# DazzeLiteSch.net
KiCad netlist of a schematic drawn in EAGLE
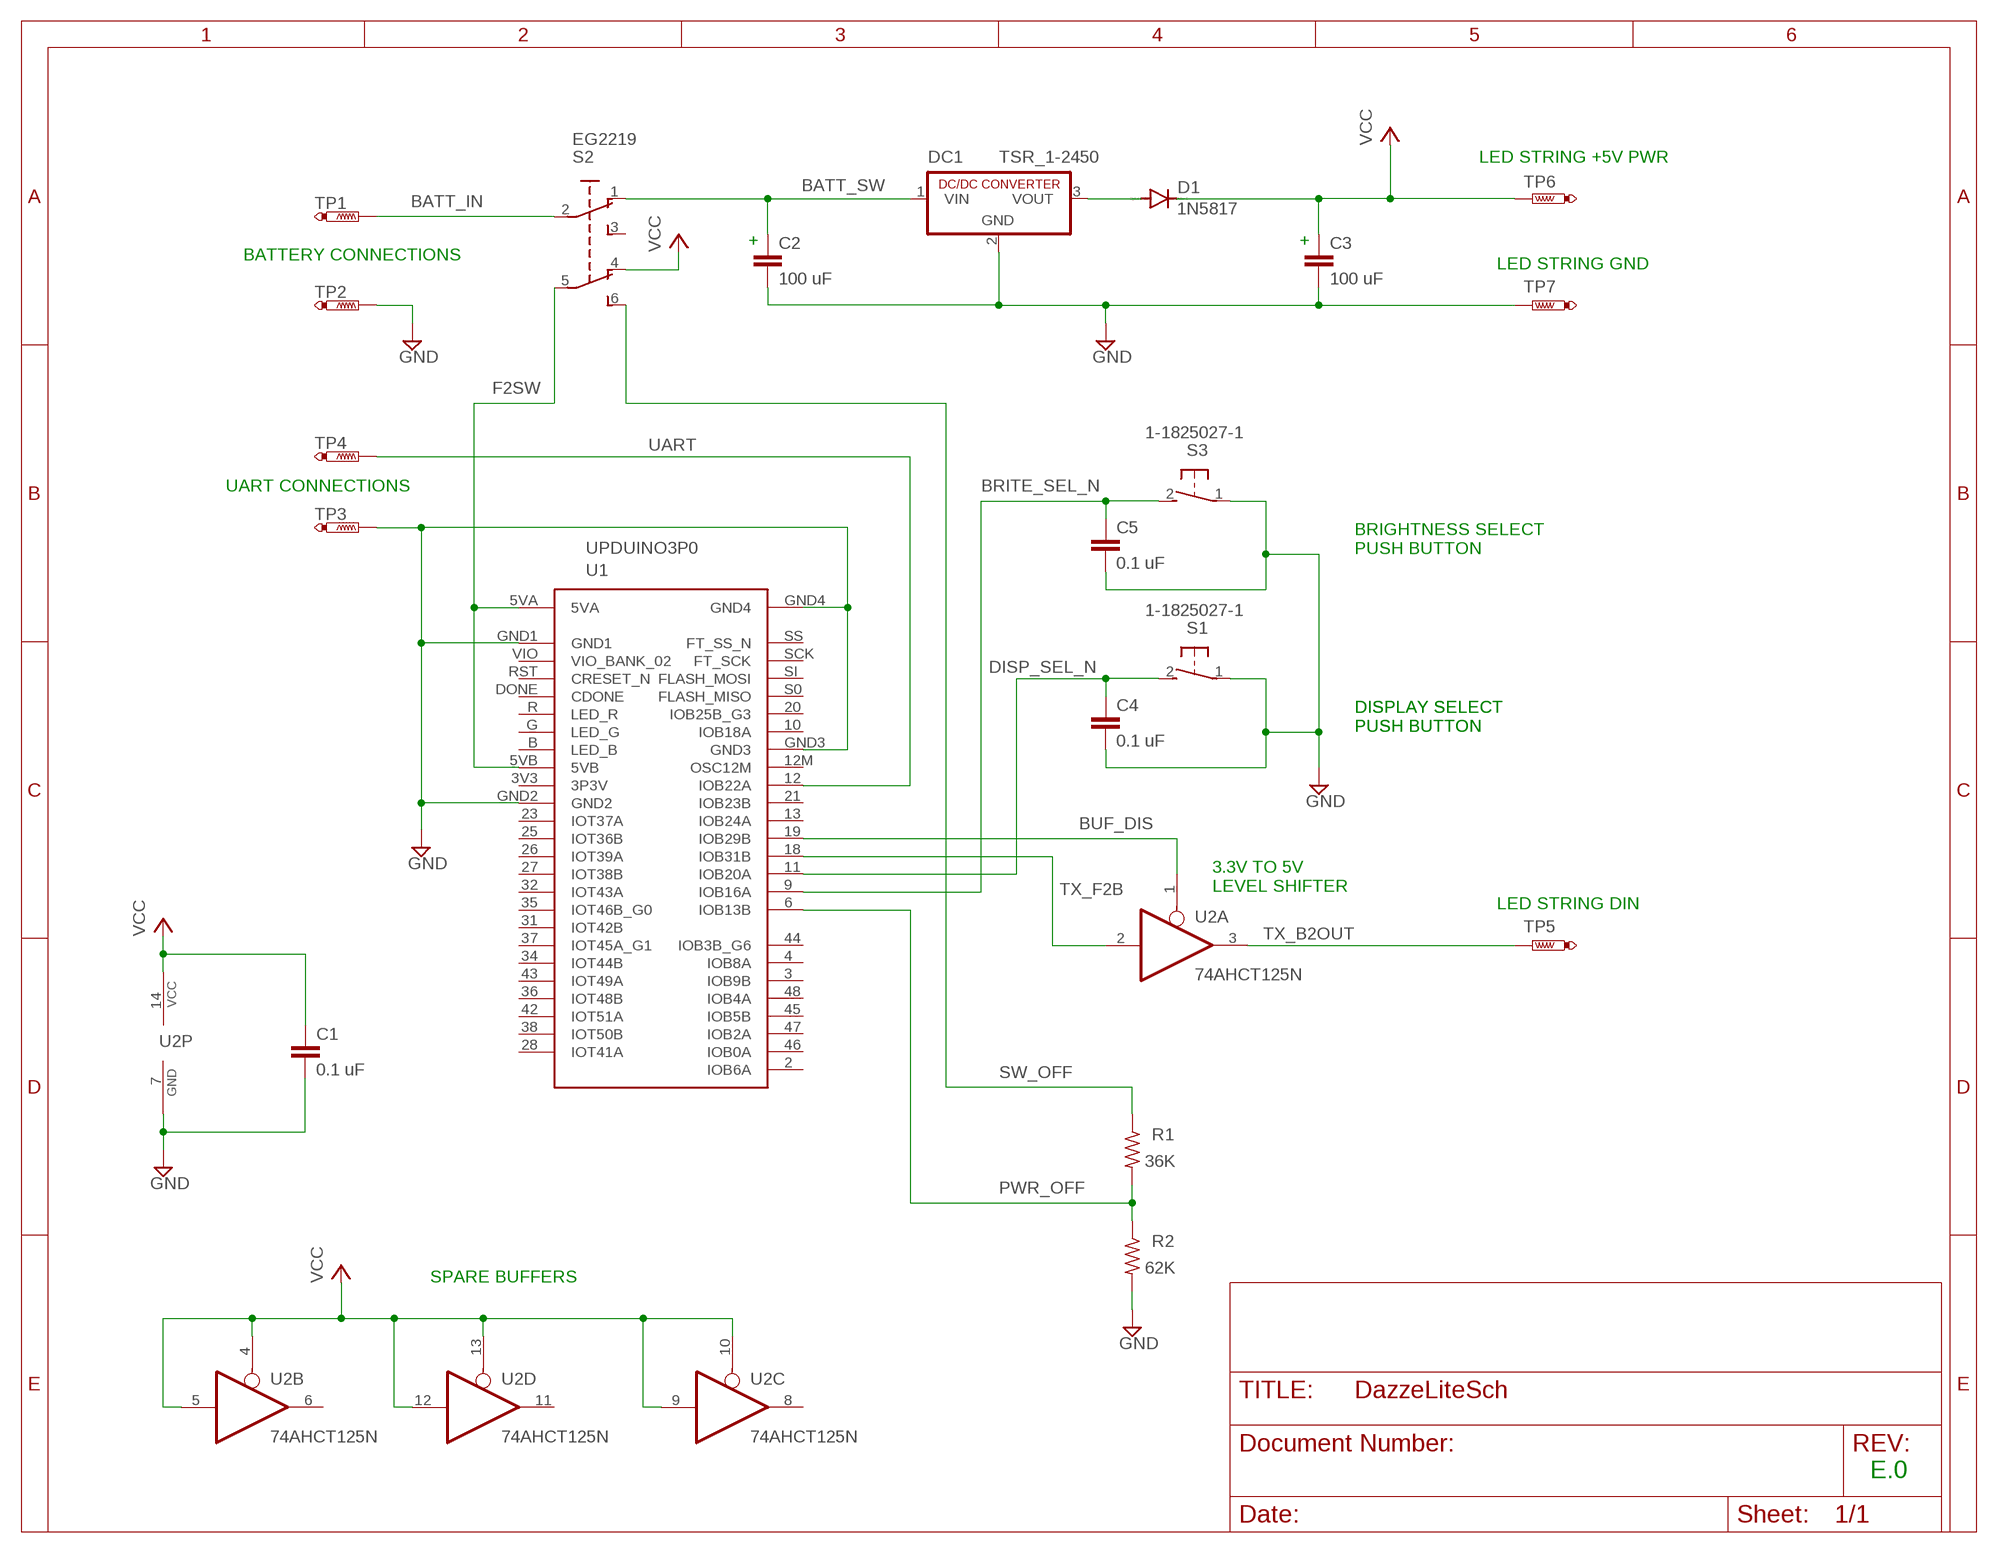
[diagram p0: schematic, sheet 1]

(export (version "E")
  (design (tool "Eeschema 10.0.6"))
  (components
    (comp (ref "C1")
      (value "0.1 uF")
      (footprint "eagle-import:C2.5-3")
      (libsource (lib "eagle-import") (part "C2,5-3"))
    )
    (comp (ref "C2")
      (value "100 uF")
      (footprint "eagle-import:C2.5-6")
      (libsource (lib "eagle-import") (part "C2.5/6"))
    )
    (comp (ref "C3")
      (value "100 uF")
      (footprint "eagle-import:C2.5-6")
      (libsource (lib "eagle-import") (part "C2.5/6"))
    )
    (comp (ref "C4")
      (value "0.1 uF")
      (footprint "eagle-import:C2.5-3")
      (libsource (lib "eagle-import") (part "C2,5-3"))
    )
    (comp (ref "C5")
      (value "0.1 uF")
      (footprint "eagle-import:C2.5-3")
      (libsource (lib "eagle-import") (part "C2,5-3"))
    )
    (comp (ref "D1")
      (value "1N5817")
      (footprint "eagle-import:DO41-10")
      (libsource (lib "eagle-import") (part "DIODE-DO41-10"))
    )
    (comp (ref "DC1")
      (value "TSR_1-2450")
      (footprint "eagle-import:SIP3")
      (libsource (lib "eagle-import") (part "TSR_1-2450"))
    )
    (comp (ref "R1")
      (value "36K")
      (footprint "eagle-import:0204_7")
      (libsource (lib "eagle-import") (part "R-US_0204/7"))
    )
    (comp (ref "R2")
      (value "62K")
      (footprint "eagle-import:0204_7")
      (libsource (lib "eagle-import") (part "R-US_0204/7"))
    )
    (comp (ref "S1")
      (value "1-1825027-1")
      (footprint "eagle-import:B3F-31XX")
      (libsource (lib "eagle-import") (part "1-1825027-1"))
    )
    (comp (ref "S2")
      (value "EG2219")
      (footprint "eagle-import:DPDT157")
      (libsource (lib "eagle-import") (part "EG2219"))
    )
    (comp (ref "S3")
      (value "1-1825027-1")
      (footprint "eagle-import:B3F-31XX")
      (libsource (lib "eagle-import") (part "1-1825027-1"))
    )
    (comp (ref "TP1")
      (value "PTR1PAD1-13")
      (footprint "eagle-import:P1-13")
      (libsource (lib "eagle-import") (part "PTR1PAD1-13"))
    )
    (comp (ref "TP2")
      (value "PTR1PAD1-13")
      (footprint "eagle-import:P1-13")
      (libsource (lib "eagle-import") (part "PTR1PAD1-13"))
    )
    (comp (ref "TP3")
      (value "PTR1PAD1-13")
      (footprint "eagle-import:P1-13")
      (libsource (lib "eagle-import") (part "PTR1PAD1-13"))
    )
    (comp (ref "TP4")
      (value "PTR1PAD1-13")
      (footprint "eagle-import:P1-13")
      (libsource (lib "eagle-import") (part "PTR1PAD1-13"))
    )
    (comp (ref "TP5")
      (value "PTR1PAD1-13")
      (footprint "eagle-import:P1-13")
      (libsource (lib "eagle-import") (part "PTR1PAD1-13"))
    )
    (comp (ref "TP6")
      (value "PTR1PAD1-13")
      (footprint "eagle-import:P1-13")
      (libsource (lib "eagle-import") (part "PTR1PAD1-13"))
    )
    (comp (ref "TP7")
      (value "PTR1PAD1-13")
      (footprint "eagle-import:P1-13")
      (libsource (lib "eagle-import") (part "PTR1PAD1-13"))
    )
    (comp (ref "U1")
      (value "UPDUINO3P0")
      (footprint "eagle-import:UPDUINO3P0")
      (libsource (lib "eagle-import") (part "UPDUINO3P0"))
    )
    (comp (ref "U2")
      (value "74AHCT125N")
      (footprint "eagle-import:DIL14")
      (libsource (lib "eagle-import") (part "74125NAHCT"))
    )
  )
  (nets
    (net (code "1") (name "/BATT_IN") (class "Default")
      (node (ref "S2") (pin "2") (pinfunction "P_2") (pintype "passive"))
      (node (ref "TP1") (pin "TP") (pinfunction "TP_TP") (pintype "input"))
    )
    (net (code "2") (name "/BATT_SW") (class "Default")
      (node (ref "C2") (pin "1") (pinfunction "1_1") (pintype "passive"))
      (node (ref "DC1") (pin "1") (pinfunction "VIN_1") (pintype "passive"))
      (node (ref "S2") (pin "1") (pinfunction "O_1") (pintype "passive"))
    )
    (net (code "3") (name "/BRITE_SEL_N") (class "Default")
      (node (ref "C5") (pin "1") (pinfunction "1_1") (pintype "passive"))
      (node (ref "S3") (pin "2") (pinfunction "S_2") (pintype "passive"))
      (node (ref "U1") (pin "9") (pinfunction "IOB16A_9") (pintype "bidirectional"))
    )
    (net (code "4") (name "/BUF_DIS") (class "Default")
      (node (ref "U1") (pin "19") (pinfunction "IOB29B_19") (pintype "bidirectional"))
      (node (ref "U2") (pin "1") (pinfunction "OE_1") (pintype "input"))
    )
    (net (code "5") (name "/DISP_SEL_N") (class "Default")
      (node (ref "C4") (pin "1") (pinfunction "1_1") (pintype "passive"))
      (node (ref "S1") (pin "2") (pinfunction "S_2") (pintype "passive"))
      (node (ref "U1") (pin "11") (pinfunction "IOB20A_11") (pintype "bidirectional"))
    )
    (net (code "6") (name "/F2SW") (class "Default")
      (node (ref "S2") (pin "5") (pinfunction "P1_5") (pintype "passive"))
      (node (ref "U1") (pin "5VA") (pinfunction "5VA_5VA") (pintype "power_in"))
      (node (ref "U1") (pin "5VB") (pinfunction "5VB_5VB") (pintype "power_in"))
    )
    (net (code "7") (name "/PWR_OFF") (class "Default")
      (node (ref "R1") (pin "2") (pinfunction "2_2") (pintype "passive"))
      (node (ref "R2") (pin "1") (pinfunction "1_1") (pintype "passive"))
      (node (ref "U1") (pin "6") (pinfunction "IOB13B_6") (pintype "bidirectional"))
    )
    (net (code "8") (name "/SW_OFF") (class "Default")
      (node (ref "R1") (pin "1") (pinfunction "1_1") (pintype "passive"))
      (node (ref "S2") (pin "6") (pinfunction "S1_6") (pintype "passive"))
    )
    (net (code "9") (name "/TX_B2OUT") (class "Default")
      (node (ref "TP5") (pin "TP") (pinfunction "TP_TP") (pintype "input"))
      (node (ref "U2") (pin "3") (pinfunction "O_3") (pintype "tri_state"))
    )
    (net (code "10") (name "/TX_F2B") (class "Default")
      (node (ref "U1") (pin "18") (pinfunction "IOB31B_18") (pintype "bidirectional"))
      (node (ref "U2") (pin "2") (pinfunction "I_2") (pintype "input"))
    )
    (net (code "11") (name "/UART") (class "Default")
      (node (ref "TP4") (pin "TP") (pinfunction "TP_TP") (pintype "input"))
      (node (ref "U1") (pin "12") (pinfunction "IOB22A_12") (pintype "bidirectional"))
    )
    (net (code "12") (name "GND") (class "Default")
      (node (ref "C1") (pin "2") (pinfunction "2_2") (pintype "passive"))
      (node (ref "C2") (pin "2") (pinfunction "2_2") (pintype "passive"))
      (node (ref "C3") (pin "2") (pinfunction "2_2") (pintype "passive"))
      (node (ref "C4") (pin "2") (pinfunction "2_2") (pintype "passive"))
      (node (ref "C5") (pin "2") (pinfunction "2_2") (pintype "passive"))
      (node (ref "DC1") (pin "2") (pinfunction "GND_2") (pintype "passive"))
      (node (ref "R2") (pin "2") (pinfunction "2_2") (pintype "passive"))
      (node (ref "S1") (pin "1") (pinfunction "P_1") (pintype "passive"))
      (node (ref "S3") (pin "1") (pinfunction "P_1") (pintype "passive"))
      (node (ref "TP2") (pin "TP") (pinfunction "TP_TP") (pintype "input"))
      (node (ref "TP3") (pin "TP") (pinfunction "TP_TP") (pintype "input"))
      (node (ref "TP7") (pin "TP") (pinfunction "TP_TP") (pintype "input"))
      (node (ref "U1") (pin "GND1") (pinfunction "GND1_GND1") (pintype "power_in"))
      (node (ref "U1") (pin "GND2") (pinfunction "GND2_GND2") (pintype "power_in"))
      (node (ref "U1") (pin "GND3") (pinfunction "GND3_GND3") (pintype "power_in"))
      (node (ref "U1") (pin "GND4") (pinfunction "GND4_GND4") (pintype "power_in"))
      (node (ref "U2") (pin "7") (pinfunction "GND_7") (pintype "power_in"))
    )
    (net (code "13") (name "Net-(DC1-VOUT)") (class "Default")
      (node (ref "D1") (pin "A") (pinfunction "A_A") (pintype "passive"))
      (node (ref "DC1") (pin "3") (pinfunction "VOUT_3") (pintype "passive"))
    )
    (net (code "14") (name "VCC") (class "Default")
      (node (ref "C1") (pin "1") (pinfunction "1_1") (pintype "passive"))
      (node (ref "C3") (pin "1") (pinfunction "1_1") (pintype "passive"))
      (node (ref "D1") (pin "C") (pinfunction "C_C") (pintype "passive"))
      (node (ref "S2") (pin "4") (pinfunction "O1_4") (pintype "passive"))
      (node (ref "TP6") (pin "TP") (pinfunction "TP_TP") (pintype "input"))
      (node (ref "U2") (pin "10") (pinfunction "OE_10") (pintype "input"))
      (node (ref "U2") (pin "12") (pinfunction "I_12") (pintype "input"))
      (node (ref "U2") (pin "13") (pinfunction "OE_13") (pintype "input"))
      (node (ref "U2") (pin "14") (pinfunction "VCC_14") (pintype "power_in"))
      (node (ref "U2") (pin "4") (pinfunction "OE_4") (pintype "input"))
      (node (ref "U2") (pin "5") (pinfunction "I_5") (pintype "input"))
      (node (ref "U2") (pin "9") (pinfunction "I_9") (pintype "input"))
    )
    (net (code "15") (name "unconnected-(S2-S-Pad3)") (class "Default")
      (node (ref "S2") (pin "3") (pinfunction "S_3") (pintype "passive"))
    )
    (net (code "16") (name "unconnected-(U1-3P3V-Pad3V3)") (class "Default")
      (node (ref "U1") (pin "3V3") (pinfunction "3P3V_3V3") (pintype "passive"))
    )
    (net (code "17") (name "unconnected-(U1-CDONE-PadDONE)") (class "Default")
      (node (ref "U1") (pin "DONE") (pinfunction "CDONE_DONE") (pintype "bidirectional"))
    )
    (net (code "18") (name "unconnected-(U1-CRESET_N-PadRST)") (class "Default")
      (node (ref "U1") (pin "RST") (pinfunction "CRESET_N_RST") (pintype "bidirectional"))
    )
    (net (code "19") (name "unconnected-(U1-FLASH_MISO-PadS0)") (class "Default")
      (node (ref "U1") (pin "S0") (pinfunction "FLASH_MISO_S0") (pintype "bidirectional"))
    )
    (net (code "20") (name "unconnected-(U1-FLASH_MOSI-PadSI)") (class "Default")
      (node (ref "U1") (pin "SI") (pinfunction "FLASH_MOSI_SI") (pintype "bidirectional"))
    )
    (net (code "21") (name "unconnected-(U1-FT_SCK-PadSCK)") (class "Default")
      (node (ref "U1") (pin "SCK") (pinfunction "FT_SCK_SCK") (pintype "bidirectional"))
    )
    (net (code "22") (name "unconnected-(U1-FT_SS_N-PadSS)") (class "Default")
      (node (ref "U1") (pin "SS") (pinfunction "FT_SS_N_SS") (pintype "bidirectional"))
    )
    (net (code "23") (name "unconnected-(U1-IOB0A-Pad46)") (class "Default")
      (node (ref "U1") (pin "46") (pinfunction "IOB0A_46") (pintype "bidirectional"))
    )
    (net (code "24") (name "unconnected-(U1-IOB2A-Pad47)") (class "Default")
      (node (ref "U1") (pin "47") (pinfunction "IOB2A_47") (pintype "bidirectional"))
    )
    (net (code "25") (name "unconnected-(U1-IOB3B_G6-Pad44)") (class "Default")
      (node (ref "U1") (pin "44") (pinfunction "IOB3B_G6_44") (pintype "bidirectional"))
    )
    (net (code "26") (name "unconnected-(U1-IOB4A-Pad48)") (class "Default")
      (node (ref "U1") (pin "48") (pinfunction "IOB4A_48") (pintype "bidirectional"))
    )
    (net (code "27") (name "unconnected-(U1-IOB5B-Pad45)") (class "Default")
      (node (ref "U1") (pin "45") (pinfunction "IOB5B_45") (pintype "bidirectional"))
    )
    (net (code "28") (name "unconnected-(U1-IOB6A-Pad2)") (class "Default")
      (node (ref "U1") (pin "2") (pinfunction "IOB6A_2") (pintype "bidirectional"))
    )
    (net (code "29") (name "unconnected-(U1-IOB8A-Pad4)") (class "Default")
      (node (ref "U1") (pin "4") (pinfunction "IOB8A_4") (pintype "bidirectional"))
    )
    (net (code "30") (name "unconnected-(U1-IOB9B-Pad3)") (class "Default")
      (node (ref "U1") (pin "3") (pinfunction "IOB9B_3") (pintype "bidirectional"))
    )
    (net (code "31") (name "unconnected-(U1-IOB18A-Pad10)") (class "Default")
      (node (ref "U1") (pin "10") (pinfunction "IOB18A_10") (pintype "bidirectional"))
    )
    (net (code "32") (name "unconnected-(U1-IOB23B-Pad21)") (class "Default")
      (node (ref "U1") (pin "21") (pinfunction "IOB23B_21") (pintype "bidirectional"))
    )
    (net (code "33") (name "unconnected-(U1-IOB24A-Pad13)") (class "Default")
      (node (ref "U1") (pin "13") (pinfunction "IOB24A_13") (pintype "bidirectional"))
    )
    (net (code "34") (name "unconnected-(U1-IOB25B_G3-Pad20)") (class "Default")
      (node (ref "U1") (pin "20") (pinfunction "IOB25B_G3_20") (pintype "bidirectional"))
    )
    (net (code "35") (name "unconnected-(U1-IOT36B-Pad25)") (class "Default")
      (node (ref "U1") (pin "25") (pinfunction "IOT36B_25") (pintype "bidirectional"))
    )
    (net (code "36") (name "unconnected-(U1-IOT37A-Pad23)") (class "Default")
      (node (ref "U1") (pin "23") (pinfunction "IOT37A_23") (pintype "bidirectional"))
    )
    (net (code "37") (name "unconnected-(U1-IOT38B-Pad27)") (class "Default")
      (node (ref "U1") (pin "27") (pinfunction "IOT38B_27") (pintype "bidirectional"))
    )
    (net (code "38") (name "unconnected-(U1-IOT39A-Pad26)") (class "Default")
      (node (ref "U1") (pin "26") (pinfunction "IOT39A_26") (pintype "bidirectional"))
    )
    (net (code "39") (name "unconnected-(U1-IOT41A-Pad28)") (class "Default")
      (node (ref "U1") (pin "28") (pinfunction "IOT41A_28") (pintype "bidirectional"))
    )
    (net (code "40") (name "unconnected-(U1-IOT42B-Pad31)") (class "Default")
      (node (ref "U1") (pin "31") (pinfunction "IOT42B_31") (pintype "bidirectional"))
    )
    (net (code "41") (name "unconnected-(U1-IOT43A-Pad32)") (class "Default")
      (node (ref "U1") (pin "32") (pinfunction "IOT43A_32") (pintype "bidirectional"))
    )
    (net (code "42") (name "unconnected-(U1-IOT44B-Pad34)") (class "Default")
      (node (ref "U1") (pin "34") (pinfunction "IOT44B_34") (pintype "bidirectional"))
    )
    (net (code "43") (name "unconnected-(U1-IOT45A_G1-Pad37)") (class "Default")
      (node (ref "U1") (pin "37") (pinfunction "IOT45A_G1_37") (pintype "bidirectional"))
    )
    (net (code "44") (name "unconnected-(U1-IOT46B_G0-Pad35)") (class "Default")
      (node (ref "U1") (pin "35") (pinfunction "IOT46B_G0_35") (pintype "bidirectional"))
    )
    (net (code "45") (name "unconnected-(U1-IOT48B-Pad36)") (class "Default")
      (node (ref "U1") (pin "36") (pinfunction "IOT48B_36") (pintype "bidirectional"))
    )
    (net (code "46") (name "unconnected-(U1-IOT49A-Pad43)") (class "Default")
      (node (ref "U1") (pin "43") (pinfunction "IOT49A_43") (pintype "bidirectional"))
    )
    (net (code "47") (name "unconnected-(U1-IOT50B-Pad38)") (class "Default")
      (node (ref "U1") (pin "38") (pinfunction "IOT50B_38") (pintype "bidirectional"))
    )
    (net (code "48") (name "unconnected-(U1-IOT51A-Pad42)") (class "Default")
      (node (ref "U1") (pin "42") (pinfunction "IOT51A_42") (pintype "bidirectional"))
    )
    (net (code "49") (name "unconnected-(U1-LED_B-PadB)") (class "Default")
      (node (ref "U1") (pin "B") (pinfunction "LED_B_B") (pintype "bidirectional"))
    )
    (net (code "50") (name "unconnected-(U1-LED_G-PadG)") (class "Default")
      (node (ref "U1") (pin "G") (pinfunction "LED_G_G") (pintype "bidirectional"))
    )
    (net (code "51") (name "unconnected-(U1-LED_R-PadR)") (class "Default")
      (node (ref "U1") (pin "R") (pinfunction "LED_R_R") (pintype "bidirectional"))
    )
    (net (code "52") (name "unconnected-(U1-OSC12M-Pad12M)") (class "Default")
      (node (ref "U1") (pin "12M") (pinfunction "OSC12M_12M") (pintype "bidirectional"))
    )
    (net (code "53") (name "unconnected-(U1-VIO_BANK_02-PadVIO)") (class "Default")
      (node (ref "U1") (pin "VIO") (pinfunction "VIO_BANK_02_VIO") (pintype "bidirectional"))
    )
    (net (code "54") (name "unconnected-(U2B-O-Pad6)") (class "Default")
      (node (ref "U2") (pin "6") (pinfunction "O_6") (pintype "tri_state"))
    )
    (net (code "55") (name "unconnected-(U2C-O-Pad8)") (class "Default")
      (node (ref "U2") (pin "8") (pinfunction "O_8") (pintype "tri_state"))
    )
    (net (code "56") (name "unconnected-(U2D-O-Pad11)") (class "Default")
      (node (ref "U2") (pin "11") (pinfunction "O_11") (pintype "tri_state"))
    )
  )
)
